# FPGA_Banks_224_225_226_227_228.net
KiCad netlist of a schematic drawn in Altium Designer
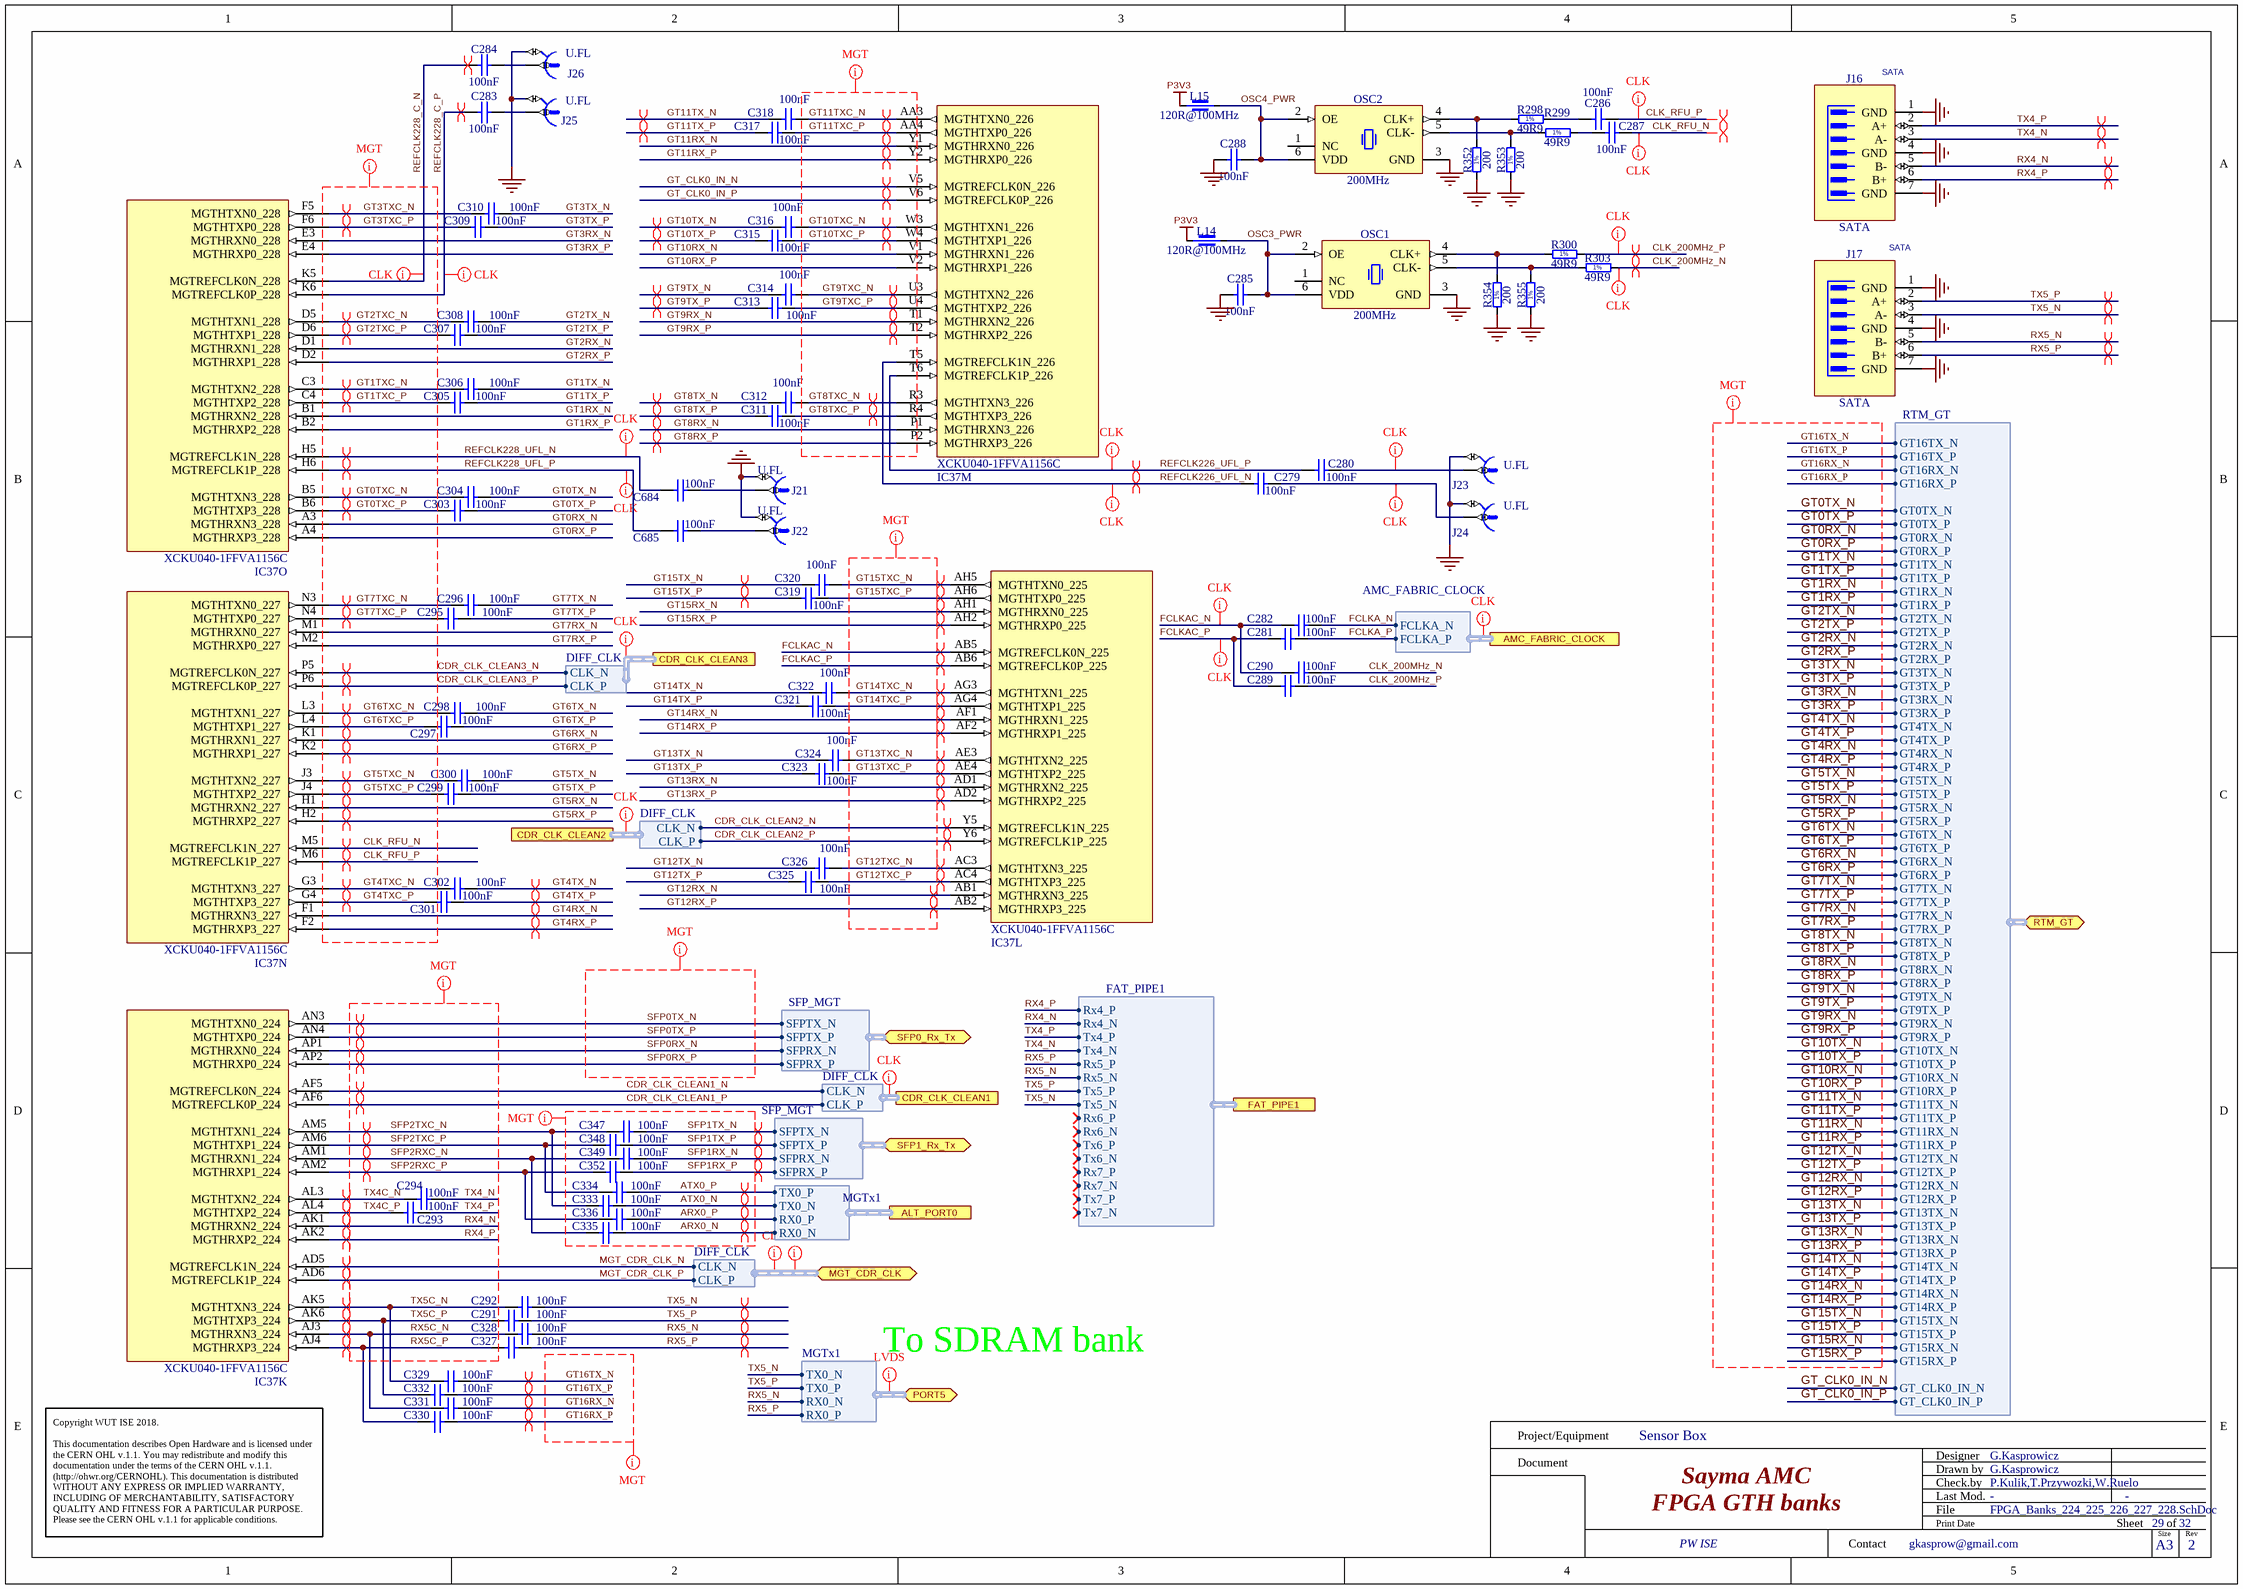
[diagram p0: FPGA_Banks_224_225_226_227_228.SchDoc]

(export (version "E")
  (design (tool "Eeschema 10.0.6"))
  (components
    (comp (ref "C279")
      (value "100nF")
      (footprint "CAPC0603X33N")
      (description "Non-polarised capacitor")
      (fields
        (field (name "MANUFACTURER PART NUMBER") "CC0201_100NF_6.3V_10%_X5R")
        (field (name "MANUFACTURER") "GENERIC")
        (field (name "AUTHOR") "CERN DEM JLC")
      )
      (libsource (lib "Capacitors") (part "Capacitor - non polarized"))
    )
    (comp (ref "C280")
      (value "100nF")
      (footprint "CAPC0603X33N")
      (description "Non-polarised capacitor")
      (fields
        (field (name "MANUFACTURER PART NUMBER") "CC0201_100NF_6.3V_10%_X5R")
        (field (name "MANUFACTURER") "GENERIC")
        (field (name "AUTHOR") "CERN DEM JLC")
      )
      (libsource (lib "Capacitors") (part "Capacitor - non polarized"))
    )
    (comp (ref "C281")
      (value "100nF")
      (footprint "CAPC0603X33N")
      (description "Non-polarised capacitor")
      (fields
        (field (name "MANUFACTURER PART NUMBER") "CC0201_100NF_6.3V_10%_X5R")
        (field (name "MANUFACTURER") "GENERIC")
        (field (name "AUTHOR") "CERN DEM JLC")
      )
      (libsource (lib "Capacitors") (part "Capacitor - non polarized"))
    )
    (comp (ref "C282")
      (value "100nF")
      (footprint "CAPC0603X33N")
      (description "Non-polarised capacitor")
      (fields
        (field (name "MANUFACTURER PART NUMBER") "CC0201_100NF_6.3V_10%_X5R")
        (field (name "MANUFACTURER") "GENERIC")
        (field (name "AUTHOR") "CERN DEM JLC")
      )
      (libsource (lib "Capacitors") (part "Capacitor - non polarized"))
    )
    (comp (ref "C283")
      (value "100nF")
      (footprint "CAPC0603X33N")
      (description "Non-polarised capacitor")
      (fields
        (field (name "MANUFACTURER PART NUMBER") "CC0201_100NF_6.3V_10%_X5R")
        (field (name "MANUFACTURER") "GENERIC")
        (field (name "AUTHOR") "CERN DEM JLC")
      )
      (libsource (lib "Capacitors") (part "Capacitor - non polarized"))
    )
    (comp (ref "C284")
      (value "100nF")
      (footprint "CAPC0603X33N")
      (description "Non-polarised capacitor")
      (fields
        (field (name "MANUFACTURER PART NUMBER") "CC0201_100NF_6.3V_10%_X5R")
        (field (name "MANUFACTURER") "GENERIC")
        (field (name "AUTHOR") "CERN DEM JLC")
      )
      (libsource (lib "Capacitors") (part "Capacitor - non polarized"))
    )
    (comp (ref "C285")
      (value "100nF")
      (footprint "CAPC0603X33N")
      (description "Non-polarised capacitor")
      (fields
        (field (name "MANUFACTURER PART NUMBER") "CC0201_100NF_6.3V_10%_X5R")
        (field (name "MANUFACTURER") "GENERIC")
        (field (name "AUTHOR") "CERN DEM JLC")
      )
      (libsource (lib "Capacitors") (part "Capacitor - non polarized"))
    )
    (comp (ref "C286")
      (value "100nF")
      (footprint "CAPC0603X33N")
      (description "Non-polarised capacitor")
      (fields
        (field (name "MANUFACTURER PART NUMBER") "CC0201_100NF_6.3V_10%_X5R")
        (field (name "MANUFACTURER") "GENERIC")
        (field (name "AUTHOR") "CERN DEM JLC")
      )
      (libsource (lib "Capacitors") (part "Capacitor - non polarized"))
    )
    (comp (ref "C287")
      (value "100nF")
      (footprint "CAPC0603X33N")
      (description "Non-polarised capacitor")
      (fields
        (field (name "MANUFACTURER PART NUMBER") "CC0201_100NF_6.3V_10%_X5R")
        (field (name "MANUFACTURER") "GENERIC")
        (field (name "AUTHOR") "CERN DEM JLC")
      )
      (libsource (lib "Capacitors") (part "Capacitor - non polarized"))
    )
    (comp (ref "C288")
      (value "100nF")
      (footprint "CAPC0603X33N")
      (description "Non-polarised capacitor")
      (fields
        (field (name "MANUFACTURER PART NUMBER") "CC0201_100NF_6.3V_10%_X5R")
        (field (name "MANUFACTURER") "GENERIC")
        (field (name "AUTHOR") "CERN DEM JLC")
      )
      (libsource (lib "Capacitors") (part "Capacitor - non polarized"))
    )
    (comp (ref "C289")
      (value "100nF")
      (footprint "CAPC0603X33N")
      (description "Non-polarised capacitor")
      (fields
        (field (name "MANUFACTURER PART NUMBER") "CC0201_100NF_6.3V_10%_X5R")
        (field (name "MANUFACTURER") "GENERIC")
        (field (name "AUTHOR") "CERN DEM JLC")
      )
      (libsource (lib "Capacitors") (part "Capacitor - non polarized"))
    )
    (comp (ref "C290")
      (value "100nF")
      (footprint "CAPC0603X33N")
      (description "Non-polarised capacitor")
      (fields
        (field (name "MANUFACTURER PART NUMBER") "CC0201_100NF_6.3V_10%_X5R")
        (field (name "MANUFACTURER") "GENERIC")
        (field (name "AUTHOR") "CERN DEM JLC")
      )
      (libsource (lib "Capacitors") (part "Capacitor - non polarized"))
    )
    (comp (ref "C291")
      (value "100nF")
      (footprint "CAPC0603X33N")
      (description "Non-polarised capacitor")
      (fields
        (field (name "MANUFACTURER PART NUMBER") "CC0201_100NF_6.3V_10%_X5R")
        (field (name "MANUFACTURER") "GENERIC")
        (field (name "AUTHOR") "CERN DEM JLC")
      )
      (libsource (lib "Capacitors") (part "Capacitor - non polarized"))
    )
    (comp (ref "C292")
      (value "100nF")
      (footprint "CAPC0603X33N")
      (description "Non-polarised capacitor")
      (fields
        (field (name "MANUFACTURER PART NUMBER") "CC0201_100NF_6.3V_10%_X5R")
        (field (name "MANUFACTURER") "GENERIC")
        (field (name "AUTHOR") "CERN DEM JLC")
      )
      (libsource (lib "Capacitors") (part "Capacitor - non polarized"))
    )
    (comp (ref "C293")
      (value "100nF")
      (footprint "CAPC0603X33N")
      (description "Non-polarised capacitor")
      (fields
        (field (name "MANUFACTURER PART NUMBER") "CC0201_100NF_6.3V_10%_X5R")
        (field (name "MANUFACTURER") "GENERIC")
        (field (name "AUTHOR") "CERN DEM JLC")
      )
      (libsource (lib "Capacitors") (part "Capacitor - non polarized"))
    )
    (comp (ref "C294")
      (value "100nF")
      (footprint "CAPC0603X33N")
      (description "Non-polarised capacitor")
      (fields
        (field (name "MANUFACTURER PART NUMBER") "CC0201_100NF_6.3V_10%_X5R")
        (field (name "MANUFACTURER") "GENERIC")
        (field (name "AUTHOR") "CERN DEM JLC")
      )
      (libsource (lib "Capacitors") (part "Capacitor - non polarized"))
    )
    (comp (ref "C295")
      (value "100nF")
      (footprint "CAPC0603X33N")
      (description "Non-polarised capacitor")
      (fields
        (field (name "MANUFACTURER PART NUMBER") "CC0201_100NF_6.3V_10%_X5R")
        (field (name "MANUFACTURER") "GENERIC")
        (field (name "AUTHOR") "CERN DEM JLC")
      )
      (libsource (lib "Capacitors") (part "Capacitor - non polarized"))
    )
    (comp (ref "C296")
      (value "100nF")
      (footprint "CAPC0603X33N")
      (description "Non-polarised capacitor")
      (fields
        (field (name "MANUFACTURER PART NUMBER") "CC0201_100NF_6.3V_10%_X5R")
        (field (name "MANUFACTURER") "GENERIC")
        (field (name "AUTHOR") "CERN DEM JLC")
      )
      (libsource (lib "Capacitors") (part "Capacitor - non polarized"))
    )
    (comp (ref "C297")
      (value "100nF")
      (footprint "CAPC0603X33N")
      (description "Non-polarised capacitor")
      (fields
        (field (name "MANUFACTURER PART NUMBER") "CC0201_100NF_6.3V_10%_X5R")
        (field (name "MANUFACTURER") "GENERIC")
        (field (name "AUTHOR") "CERN DEM JLC")
      )
      (libsource (lib "Capacitors") (part "Capacitor - non polarized"))
    )
    (comp (ref "C298")
      (value "100nF")
      (footprint "CAPC0603X33N")
      (description "Non-polarised capacitor")
      (fields
        (field (name "MANUFACTURER PART NUMBER") "CC0201_100NF_6.3V_10%_X5R")
        (field (name "MANUFACTURER") "GENERIC")
        (field (name "AUTHOR") "CERN DEM JLC")
      )
      (libsource (lib "Capacitors") (part "Capacitor - non polarized"))
    )
    (comp (ref "C299")
      (value "100nF")
      (footprint "CAPC0603X33N")
      (description "Non-polarised capacitor")
      (fields
        (field (name "MANUFACTURER PART NUMBER") "CC0201_100NF_6.3V_10%_X5R")
        (field (name "MANUFACTURER") "GENERIC")
        (field (name "AUTHOR") "CERN DEM JLC")
      )
      (libsource (lib "Capacitors") (part "Capacitor - non polarized"))
    )
    (comp (ref "C300")
      (value "100nF")
      (footprint "CAPC0603X33N")
      (description "Non-polarised capacitor")
      (fields
        (field (name "MANUFACTURER PART NUMBER") "CC0201_100NF_6.3V_10%_X5R")
        (field (name "MANUFACTURER") "GENERIC")
        (field (name "AUTHOR") "CERN DEM JLC")
      )
      (libsource (lib "Capacitors") (part "Capacitor - non polarized"))
    )
    (comp (ref "C301")
      (value "100nF")
      (footprint "CAPC0603X33N")
      (description "Non-polarised capacitor")
      (fields
        (field (name "MANUFACTURER PART NUMBER") "CC0201_100NF_6.3V_10%_X5R")
        (field (name "MANUFACTURER") "GENERIC")
        (field (name "AUTHOR") "CERN DEM JLC")
      )
      (libsource (lib "Capacitors") (part "Capacitor - non polarized"))
    )
    (comp (ref "C302")
      (value "100nF")
      (footprint "CAPC0603X33N")
      (description "Non-polarised capacitor")
      (fields
        (field (name "MANUFACTURER PART NUMBER") "CC0201_100NF_6.3V_10%_X5R")
        (field (name "MANUFACTURER") "GENERIC")
        (field (name "AUTHOR") "CERN DEM JLC")
      )
      (libsource (lib "Capacitors") (part "Capacitor - non polarized"))
    )
    (comp (ref "C303")
      (value "100nF")
      (footprint "CAPC0603X33N")
      (description "Non-polarised capacitor")
      (fields
        (field (name "MANUFACTURER PART NUMBER") "CC0201_100NF_6.3V_10%_X5R")
        (field (name "MANUFACTURER") "GENERIC")
        (field (name "AUTHOR") "CERN DEM JLC")
      )
      (libsource (lib "Capacitors") (part "Capacitor - non polarized"))
    )
    (comp (ref "C304")
      (value "100nF")
      (footprint "CAPC0603X33N")
      (description "Non-polarised capacitor")
      (fields
        (field (name "MANUFACTURER PART NUMBER") "CC0201_100NF_6.3V_10%_X5R")
        (field (name "MANUFACTURER") "GENERIC")
        (field (name "AUTHOR") "CERN DEM JLC")
      )
      (libsource (lib "Capacitors") (part "Capacitor - non polarized"))
    )
    (comp (ref "C305")
      (value "100nF")
      (footprint "CAPC0603X33N")
      (description "Non-polarised capacitor")
      (fields
        (field (name "MANUFACTURER PART NUMBER") "CC0201_100NF_6.3V_10%_X5R")
        (field (name "MANUFACTURER") "GENERIC")
        (field (name "AUTHOR") "CERN DEM JLC")
      )
      (libsource (lib "Capacitors") (part "Capacitor - non polarized"))
    )
    (comp (ref "C306")
      (value "100nF")
      (footprint "CAPC0603X33N")
      (description "Non-polarised capacitor")
      (fields
        (field (name "MANUFACTURER PART NUMBER") "CC0201_100NF_6.3V_10%_X5R")
        (field (name "MANUFACTURER") "GENERIC")
        (field (name "AUTHOR") "CERN DEM JLC")
      )
      (libsource (lib "Capacitors") (part "Capacitor - non polarized"))
    )
    (comp (ref "C307")
      (value "100nF")
      (footprint "CAPC0603X33N")
      (description "Non-polarised capacitor")
      (fields
        (field (name "MANUFACTURER PART NUMBER") "CC0201_100NF_6.3V_10%_X5R")
        (field (name "MANUFACTURER") "GENERIC")
        (field (name "AUTHOR") "CERN DEM JLC")
      )
      (libsource (lib "Capacitors") (part "Capacitor - non polarized"))
    )
    (comp (ref "C308")
      (value "100nF")
      (footprint "CAPC0603X33N")
      (description "Non-polarised capacitor")
      (fields
        (field (name "MANUFACTURER PART NUMBER") "CC0201_100NF_6.3V_10%_X5R")
        (field (name "MANUFACTURER") "GENERIC")
        (field (name "AUTHOR") "CERN DEM JLC")
      )
      (libsource (lib "Capacitors") (part "Capacitor - non polarized"))
    )
    (comp (ref "C309")
      (value "100nF")
      (footprint "CAPC0603X33N")
      (description "Non-polarised capacitor")
      (fields
        (field (name "MANUFACTURER PART NUMBER") "CC0201_100NF_6.3V_10%_X5R")
        (field (name "MANUFACTURER") "GENERIC")
        (field (name "AUTHOR") "CERN DEM JLC")
      )
      (libsource (lib "Capacitors") (part "Capacitor - non polarized"))
    )
    (comp (ref "C310")
      (value "100nF")
      (footprint "CAPC0603X33N")
      (description "Non-polarised capacitor")
      (fields
        (field (name "MANUFACTURER PART NUMBER") "CC0201_100NF_6.3V_10%_X5R")
        (field (name "MANUFACTURER") "GENERIC")
        (field (name "AUTHOR") "CERN DEM JLC")
      )
      (libsource (lib "Capacitors") (part "Capacitor - non polarized"))
    )
    (comp (ref "C311")
      (value "100nF")
      (footprint "CAPC0603X33N")
      (description "Non-polarised capacitor")
      (fields
        (field (name "MANUFACTURER PART NUMBER") "CC0201_100NF_6.3V_10%_X5R")
        (field (name "MANUFACTURER") "GENERIC")
        (field (name "AUTHOR") "CERN DEM JLC")
      )
      (libsource (lib "Capacitors") (part "Capacitor - non polarized"))
    )
    (comp (ref "C312")
      (value "100nF")
      (footprint "CAPC0603X33N")
      (description "Non-polarised capacitor")
      (fields
        (field (name "MANUFACTURER PART NUMBER") "CC0201_100NF_6.3V_10%_X5R")
        (field (name "MANUFACTURER") "GENERIC")
        (field (name "AUTHOR") "CERN DEM JLC")
      )
      (libsource (lib "Capacitors") (part "Capacitor - non polarized"))
    )
    (comp (ref "C313")
      (value "100nF")
      (footprint "CAPC0603X33N")
      (description "Non-polarised capacitor")
      (fields
        (field (name "MANUFACTURER PART NUMBER") "CC0201_100NF_6.3V_10%_X5R")
        (field (name "MANUFACTURER") "GENERIC")
        (field (name "AUTHOR") "CERN DEM JLC")
      )
      (libsource (lib "Capacitors") (part "Capacitor - non polarized"))
    )
    (comp (ref "C314")
      (value "100nF")
      (footprint "CAPC0603X33N")
      (description "Non-polarised capacitor")
      (fields
        (field (name "MANUFACTURER PART NUMBER") "CC0201_100NF_6.3V_10%_X5R")
        (field (name "MANUFACTURER") "GENERIC")
        (field (name "AUTHOR") "CERN DEM JLC")
      )
      (libsource (lib "Capacitors") (part "Capacitor - non polarized"))
    )
    (comp (ref "C315")
      (value "100nF")
      (footprint "CAPC0603X33N")
      (description "Non-polarised capacitor")
      (fields
        (field (name "MANUFACTURER PART NUMBER") "CC0201_100NF_6.3V_10%_X5R")
        (field (name "MANUFACTURER") "GENERIC")
        (field (name "AUTHOR") "CERN DEM JLC")
      )
      (libsource (lib "Capacitors") (part "Capacitor - non polarized"))
    )
    (comp (ref "C316")
      (value "100nF")
      (footprint "CAPC0603X33N")
      (description "Non-polarised capacitor")
      (fields
        (field (name "MANUFACTURER PART NUMBER") "CC0201_100NF_6.3V_10%_X5R")
        (field (name "MANUFACTURER") "GENERIC")
        (field (name "AUTHOR") "CERN DEM JLC")
      )
      (libsource (lib "Capacitors") (part "Capacitor - non polarized"))
    )
    (comp (ref "C317")
      (value "100nF")
      (footprint "CAPC0603X33N")
      (description "Non-polarised capacitor")
      (fields
        (field (name "MANUFACTURER PART NUMBER") "CC0201_100NF_6.3V_10%_X5R")
        (field (name "MANUFACTURER") "GENERIC")
        (field (name "AUTHOR") "CERN DEM JLC")
      )
      (libsource (lib "Capacitors") (part "Capacitor - non polarized"))
    )
    (comp (ref "C318")
      (value "100nF")
      (footprint "CAPC0603X33N")
      (description "Non-polarised capacitor")
      (fields
        (field (name "MANUFACTURER PART NUMBER") "CC0201_100NF_6.3V_10%_X5R")
        (field (name "MANUFACTURER") "GENERIC")
        (field (name "AUTHOR") "CERN DEM JLC")
      )
      (libsource (lib "Capacitors") (part "Capacitor - non polarized"))
    )
    (comp (ref "C319")
      (value "100nF")
      (footprint "CAPC0603X33N")
      (description "Non-polarised capacitor")
      (fields
        (field (name "MANUFACTURER PART NUMBER") "CC0201_100NF_6.3V_10%_X5R")
        (field (name "MANUFACTURER") "GENERIC")
        (field (name "AUTHOR") "CERN DEM JLC")
      )
      (libsource (lib "Capacitors") (part "Capacitor - non polarized"))
    )
    (comp (ref "C320")
      (value "100nF")
      (footprint "CAPC0603X33N")
      (description "Non-polarised capacitor")
      (fields
        (field (name "MANUFACTURER PART NUMBER") "CC0201_100NF_6.3V_10%_X5R")
        (field (name "MANUFACTURER") "GENERIC")
        (field (name "AUTHOR") "CERN DEM JLC")
      )
      (libsource (lib "Capacitors") (part "Capacitor - non polarized"))
    )
    (comp (ref "C321")
      (value "100nF")
      (footprint "CAPC0603X33N")
      (description "Non-polarised capacitor")
      (fields
        (field (name "MANUFACTURER PART NUMBER") "CC0201_100NF_6.3V_10%_X5R")
        (field (name "MANUFACTURER") "GENERIC")
        (field (name "AUTHOR") "CERN DEM JLC")
      )
      (libsource (lib "Capacitors") (part "Capacitor - non polarized"))
    )
    (comp (ref "C322")
      (value "100nF")
      (footprint "CAPC0603X33N")
      (description "Non-polarised capacitor")
      (fields
        (field (name "MANUFACTURER PART NUMBER") "CC0201_100NF_6.3V_10%_X5R")
        (field (name "MANUFACTURER") "GENERIC")
        (field (name "AUTHOR") "CERN DEM JLC")
      )
      (libsource (lib "Capacitors") (part "Capacitor - non polarized"))
    )
    (comp (ref "C323")
      (value "100nF")
      (footprint "CAPC0603X33N")
      (description "Non-polarised capacitor")
      (fields
        (field (name "MANUFACTURER PART NUMBER") "CC0201_100NF_6.3V_10%_X5R")
        (field (name "MANUFACTURER") "GENERIC")
        (field (name "AUTHOR") "CERN DEM JLC")
      )
      (libsource (lib "Capacitors") (part "Capacitor - non polarized"))
    )
    (comp (ref "C324")
      (value "100nF")
      (footprint "CAPC0603X33N")
      (description "Non-polarised capacitor")
      (fields
        (field (name "MANUFACTURER PART NUMBER") "CC0201_100NF_6.3V_10%_X5R")
        (field (name "MANUFACTURER") "GENERIC")
        (field (name "AUTHOR") "CERN DEM JLC")
      )
      (libsource (lib "Capacitors") (part "Capacitor - non polarized"))
    )
    (comp (ref "C325")
      (value "100nF")
      (footprint "CAPC0603X33N")
      (description "Non-polarised capacitor")
      (fields
        (field (name "MANUFACTURER PART NUMBER") "CC0201_100NF_6.3V_10%_X5R")
        (field (name "MANUFACTURER") "GENERIC")
        (field (name "AUTHOR") "CERN DEM JLC")
      )
      (libsource (lib "Capacitors") (part "Capacitor - non polarized"))
    )
    (comp (ref "C326")
      (value "100nF")
      (footprint "CAPC0603X33N")
      (description "Non-polarised capacitor")
      (fields
        (field (name "MANUFACTURER PART NUMBER") "CC0201_100NF_6.3V_10%_X5R")
        (field (name "MANUFACTURER") "GENERIC")
        (field (name "AUTHOR") "CERN DEM JLC")
      )
      (libsource (lib "Capacitors") (part "Capacitor - non polarized"))
    )
    (comp (ref "C327")
      (value "100nF")
      (footprint "CAPC0603X33N")
      (description "Non-polarised capacitor")
      (fields
        (field (name "MANUFACTURER PART NUMBER") "CC0201_100NF_6.3V_10%_X5R")
        (field (name "MANUFACTURER") "GENERIC")
        (field (name "AUTHOR") "CERN DEM JLC")
      )
      (libsource (lib "Capacitors") (part "Capacitor - non polarized"))
    )
    (comp (ref "C328")
      (value "100nF")
      (footprint "CAPC0603X33N")
      (description "Non-polarised capacitor")
      (fields
        (field (name "MANUFACTURER PART NUMBER") "CC0201_100NF_6.3V_10%_X5R")
        (field (name "MANUFACTURER") "GENERIC")
        (field (name "AUTHOR") "CERN DEM JLC")
      )
      (libsource (lib "Capacitors") (part "Capacitor - non polarized"))
    )
    (comp (ref "C329")
      (value "100nF")
      (footprint "CAPC0603X33N")
      (description "Non-polarised capacitor")
      (fields
        (field (name "MANUFACTURER PART NUMBER") "CC0201_100NF_6.3V_10%_X5R")
        (field (name "MANUFACTURER") "GENERIC")
        (field (name "AUTHOR") "CERN DEM JLC")
      )
      (libsource (lib "Capacitors") (part "Capacitor - non polarized"))
    )
    (comp (ref "C330")
      (value "100nF")
      (footprint "CAPC0603X33N")
      (description "Non-polarised capacitor")
      (fields
        (field (name "MANUFACTURER PART NUMBER") "CC0201_100NF_6.3V_10%_X5R")
        (field (name "MANUFACTURER") "GENERIC")
        (field (name "AUTHOR") "CERN DEM JLC")
      )
      (libsource (lib "Capacitors") (part "Capacitor - non polarized"))
    )
    (comp (ref "C331")
      (value "100nF")
      (footprint "CAPC0603X33N")
      (description "Non-polarised capacitor")
      (fields
        (field (name "MANUFACTURER PART NUMBER") "CC0201_100NF_6.3V_10%_X5R")
        (field (name "MANUFACTURER") "GENERIC")
        (field (name "AUTHOR") "CERN DEM JLC")
      )
      (libsource (lib "Capacitors") (part "Capacitor - non polarized"))
    )
    (comp (ref "C332")
      (value "100nF")
      (footprint "CAPC0603X33N")
      (description "Non-polarised capacitor")
      (fields
        (field (name "MANUFACTURER PART NUMBER") "CC0201_100NF_6.3V_10%_X5R")
        (field (name "MANUFACTURER") "GENERIC")
        (field (name "AUTHOR") "CERN DEM JLC")
      )
      (libsource (lib "Capacitors") (part "Capacitor - non polarized"))
    )
    (comp (ref "C333")
      (value "100nF")
      (footprint "CAPC0603X33N")
      (description "Non-polarised capacitor")
      (fields
        (field (name "MANUFACTURER PART NUMBER") "CC0201_100NF_6.3V_10%_X5R")
        (field (name "MANUFACTURER") "GENERIC")
        (field (name "AUTHOR") "CERN DEM JLC")
      )
      (libsource (lib "Capacitors") (part "Capacitor - non polarized"))
    )
    (comp (ref "C334")
      (value "100nF")
      (footprint "CAPC0603X33N")
      (description "Non-polarised capacitor")
      (fields
        (field (name "MANUFACTURER PART NUMBER") "CC0201_100NF_6.3V_10%_X5R")
        (field (name "MANUFACTURER") "GENERIC")
        (field (name "AUTHOR") "CERN DEM JLC")
      )
      (libsource (lib "Capacitors") (part "Capacitor - non polarized"))
    )
    (comp (ref "C335")
      (value "100nF")
      (footprint "CAPC0603X33N")
      (description "Non-polarised capacitor")
      (fields
        (field (name "MANUFACTURER PART NUMBER") "CC0201_100NF_6.3V_10%_X5R")
        (field (name "MANUFACTURER") "GENERIC")
        (field (name "AUTHOR") "CERN DEM JLC")
      )
      (libsource (lib "Capacitors") (part "Capacitor - non polarized"))
    )
    (comp (ref "C336")
      (value "100nF")
      (footprint "CAPC0603X33N")
      (description "Non-polarised capacitor")
      (fields
        (field (name "MANUFACTURER PART NUMBER") "CC0201_100NF_6.3V_10%_X5R")
        (field (name "MANUFACTURER") "GENERIC")
        (field (name "AUTHOR") "CERN DEM JLC")
      )
      (libsource (lib "Capacitors") (part "Capacitor - non polarized"))
    )
    (comp (ref "C347")
      (value "100nF")
      (footprint "CAPC0603X33N")
      (description "Non-polarised capacitor")
      (fields
        (field (name "MANUFACTURER PART NUMBER") "CC0201_100NF_6.3V_10%_X5R")
        (field (name "MANUFACTURER") "GENERIC")
        (field (name "AUTHOR") "CERN DEM JLC")
      )
      (libsource (lib "Capacitors") (part "Capacitor - non polarized"))
    )
    (comp (ref "C348")
      (value "100nF")
      (footprint "CAPC0603X33N")
      (description "Non-polarised capacitor")
      (fields
        (field (name "MANUFACTURER PART NUMBER") "CC0201_100NF_6.3V_10%_X5R")
        (field (name "MANUFACTURER") "GENERIC")
        (field (name "AUTHOR") "CERN DEM JLC")
      )
      (libsource (lib "Capacitors") (part "Capacitor - non polarized"))
    )
    (comp (ref "C349")
      (value "100nF")
      (footprint "CAPC0603X33N")
      (description "Non-polarised capacitor")
      (fields
        (field (name "MANUFACTURER PART NUMBER") "CC0201_100NF_6.3V_10%_X5R")
        (field (name "MANUFACTURER") "GENERIC")
        (field (name "AUTHOR") "CERN DEM JLC")
      )
      (libsource (lib "Capacitors") (part "Capacitor - non polarized"))
    )
    (comp (ref "C352")
      (value "100nF")
      (footprint "CAPC0603X33N")
      (description "Non-polarised capacitor")
      (fields
        (field (name "MANUFACTURER PART NUMBER") "CC0201_100NF_6.3V_10%_X5R")
        (field (name "MANUFACTURER") "GENERIC")
        (field (name "AUTHOR") "CERN DEM JLC")
      )
      (libsource (lib "Capacitors") (part "Capacitor - non polarized"))
    )
    (comp (ref "C684")
      (value "100nF")
      (footprint "CAPC1005X55N")
      (description "Non-polarised capacitor")
      (fields
        (field (name "MANUFACTURER PART NUMBER") "CC0402_100NF_16V_10%_X5R")
        (field (name "MANUFACTURER") "GENERIC")
        (field (name "AUTHOR") "CERN DEM JLC")
      )
      (libsource (lib "Capacitors") (part "Capacitor - non polarized"))
    )
    (comp (ref "C685")
      (value "100nF")
      (footprint "CAPC1005X55N")
      (description "Non-polarised capacitor")
      (fields
        (field (name "MANUFACTURER PART NUMBER") "CC0402_100NF_16V_10%_X5R")
        (field (name "MANUFACTURER") "GENERIC")
        (field (name "AUTHOR") "CERN DEM JLC")
      )
      (libsource (lib "Capacitors") (part "Capacitor - non polarized"))
    )
    (comp (ref "IC37")
      (value "XCKU040-1FFVA1156C")
      (footprint "BGA1156C100P34X34_3500X3500X350")
      (description "Kintex UltraScale FPGA, 520 I/O, 530K Cells, 1156-Ball BGA, Speed Grade 1, Commercial Grade")
      (fields (field (name "MANUFACTURER") "XILINX") (field (name "AUTHOR") "CERN DEM CA"))
      (libsource (lib "") (part "XCKU040-1FFVA1156C_1"))
    )
    (comp (ref "J16")
      (value "SATA")
      (footprint "MOLEX_67800-5005")
      (description "7 Pin SATA Receptacle")
      (fields
        (field (name "MANUFACTURER PART NUMBER") "67800-5005")
        (field (name "MANUFACTURER") "MOLEX")
        (field (name "AUTHOR") "CERN DEM MR")
      )
      (libsource (lib "Connectors") (part "Connector SATA 7 Male"))
    )
    (comp (ref "J17")
      (value "SATA")
      (footprint "MOLEX_67800-5005")
      (description "7 Pin SATA Receptacle")
      (fields
        (field (name "MANUFACTURER PART NUMBER") "67800-5005")
        (field (name "MANUFACTURER") "MOLEX")
        (field (name "AUTHOR") "CERN DEM MR")
      )
      (libsource (lib "Connectors") (part "Connector SATA 7 Male"))
    )
    (comp (ref "J21")
      (value "U.FL")
      (footprint "HIROSE_U.FL-R-SMT-1(10)")
      (fields
        (field (name "PART NUMBER") "HIROSE_U.FL-R-SMT-1(10)")
        (field (name "MANUFACTURER") "HIROSE (HRS)")
        (field (name "MANUFACTURER PART NUMBER") "U.FL-R-SMT-1(10)")
        (field (name "AUTHOR") "CERN DEM JLC")
      )
      (libsource (lib "Connectors") (part "Coax_1Male_1Shield"))
    )
    (comp (ref "J22")
      (value "U.FL")
      (footprint "HIROSE_U.FL-R-SMT-1(10)")
      (fields
        (field (name "PART NUMBER") "HIROSE_U.FL-R-SMT-1(10)")
        (field (name "MANUFACTURER") "HIROSE (HRS)")
        (field (name "MANUFACTURER PART NUMBER") "U.FL-R-SMT-1(10)")
        (field (name "AUTHOR") "CERN DEM JLC")
      )
      (libsource (lib "Connectors") (part "Coax_1Male_1Shield"))
    )
    (comp (ref "J23")
      (value "U.FL")
      (footprint "HIROSE_U.FL-R-SMT-1(10)")
      (fields
        (field (name "MANUFACTURER PART NUMBER") "U.FL-R-SMT-1(10)")
        (field (name "MANUFACTURER") "HIROSE (HRS)")
        (field (name "PART NUMBER") "HIROSE_U.FL-R-SMT-1(10)")
        (field (name "AUTHOR") "CERN DEM JLC")
      )
      (libsource (lib "Connectors") (part "Coax_1Male_1Shield"))
    )
    (comp (ref "J24")
      (value "U.FL")
      (footprint "HIROSE_U.FL-R-SMT-1(10)")
      (fields
        (field (name "MANUFACTURER PART NUMBER") "U.FL-R-SMT-1(10)")
        (field (name "MANUFACTURER") "HIROSE (HRS)")
        (field (name "PART NUMBER") "HIROSE_U.FL-R-SMT-1(10)")
        (field (name "AUTHOR") "CERN DEM JLC")
      )
      (libsource (lib "Connectors") (part "Coax_1Male_1Shield"))
    )
    (comp (ref "J25")
      (value "U.FL")
      (footprint "HIROSE_U.FL-R-SMT-1(10)")
      (fields
        (field (name "MANUFACTURER PART NUMBER") "U.FL-R-SMT-1(10)")
        (field (name "MANUFACTURER") "HIROSE (HRS)")
        (field (name "PART NUMBER") "HIROSE_U.FL-R-SMT-1(10)")
        (field (name "AUTHOR") "CERN DEM JLC")
      )
      (libsource (lib "Connectors") (part "Coax_1Male_1Shield"))
    )
    (comp (ref "J26")
      (value "U.FL")
      (footprint "HIROSE_U.FL-R-SMT-1(10)")
      (fields
        (field (name "MANUFACTURER PART NUMBER") "U.FL-R-SMT-1(10)")
        (field (name "MANUFACTURER") "HIROSE (HRS)")
        (field (name "PART NUMBER") "HIROSE_U.FL-R-SMT-1(10)")
        (field (name "AUTHOR") "CERN DEM JLC")
      )
      (libsource (lib "Connectors") (part "Coax_1Male_1Shield"))
    )
    (comp (ref "L14")
      (value "120R@100MHz")
      (footprint "INDC1005X55N")
      (fields
        (field (name "MANUFACTURER PART NUMBER") "BLM15PX121SN1D")
        (field (name "MANUFACTURER") "MURATA")
        (field (name "PART NUMBER") "IND0402_MURATA_BLM15PX121SN1D")
        (field (name "AUTHOR") "CERN DEM JMW")
      )
      (libsource (lib "Inductors & Transformers") (part "Ferrite Bead"))
    )
    (comp (ref "L15")
      (value "120R@100MHz")
      (footprint "INDC1005X55N")
      (fields
        (field (name "MANUFACTURER PART NUMBER") "BLM15PX121SN1D")
        (field (name "MANUFACTURER") "MURATA")
        (field (name "PART NUMBER") "IND0402_MURATA_BLM15PX121SN1D")
        (field (name "AUTHOR") "CERN DEM JMW")
      )
      (libsource (lib "Inductors & Transformers") (part "Ferrite Bead"))
    )
    (comp (ref "OSC1")
      (value "200MHz")
      (footprint "OSC_SILICON-LAB_SI510-6N(5X7)")
      (description "Crystal Oscillator 6 pins, Si510 (LVDS/LVPECL/HCSL/Dual CMOS)")
      (fields
        (field (name "MANUFACTURER PART NUMBER") "510ABA200M000AAG")
        (field (name "MANUFACTURER") "SILICON LABS")
        (field (name "AUTHOR") "GK")
      )
      (libsource (lib "LIBRARY_SCH") (part "OSC_200MHZ_SILICON-LAB_510ABA200M000AAG"))
    )
    (comp (ref "OSC2")
      (value "200MHz")
      (footprint "OSC_SILICON-LAB_SI510-6N(5X7)")
      (description "Crystal Oscillator 6 pins, Si510 (LVDS/LVPECL/HCSL/Dual CMOS)")
      (fields
        (field (name "MANUFACTURER PART NUMBER") "510ABA200M000AAG")
        (field (name "MANUFACTURER") "SILICON LABS")
        (field (name "AUTHOR") "GK")
      )
      (libsource (lib "LIBRARY_SCH") (part "OSC_200MHZ_SILICON-LAB_510ABA200M000AAG"))
    )
    (comp (ref "R298")
      (value "49R9")
      (footprint "RESC1005X40N")
      (description "Resistor - 1%")
      (fields
        (field (name "MANUFACTURER PART NUMBER") "R0402_49R9_1%_0.0625W_100PPM")
        (field (name "MANUFACTURER") "GENERIC")
        (field (name "AUTHOR") "CERN DEM JLC")
      )
      (libsource (lib "Resistors") (part "Resistor - 1%"))
    )
    (comp (ref "R299")
      (value "49R9")
      (footprint "RESC1005X40N")
      (description "Resistor - 1%")
      (fields
        (field (name "MANUFACTURER PART NUMBER") "R0402_49R9_1%_0.0625W_100PPM")
        (field (name "MANUFACTURER") "GENERIC")
        (field (name "AUTHOR") "CERN DEM JLC")
      )
      (libsource (lib "Resistors") (part "Resistor - 1%"))
    )
    (comp (ref "R300")
      (value "49R9")
      (footprint "RESC1005X40N")
      (description "Resistor - 1%")
      (fields
        (field (name "MANUFACTURER PART NUMBER") "R0402_49R9_1%_0.0625W_100PPM")
        (field (name "MANUFACTURER") "GENERIC")
        (field (name "AUTHOR") "CERN DEM JLC")
      )
      (libsource (lib "Resistors") (part "Resistor - 1%"))
    )
    (comp (ref "R303")
      (value "49R9")
      (footprint "RESC1005X40N")
      (description "Resistor - 1%")
      (fields
        (field (name "MANUFACTURER PART NUMBER") "R0402_49R9_1%_0.0625W_100PPM")
        (field (name "MANUFACTURER") "GENERIC")
        (field (name "AUTHOR") "CERN DEM JLC")
      )
      (libsource (lib "Resistors") (part "Resistor - 1%"))
    )
    (comp (ref "R352")
      (value "200")
      (footprint "RESC1005X40N")
      (description "Resistor - 1%")
      (fields
        (field (name "MANUFACTURER PART NUMBER") "R0402_200R_1%_0.0625W_100PPM")
        (field (name "MANUFACTURER") "GENERIC")
        (field (name "AUTHOR") "CERN DEM JLC")
      )
      (libsource (lib "Resistors") (part "Resistor - 1%"))
    )
    (comp (ref "R353")
      (value "200")
      (footprint "RESC1005X40N")
      (description "Resistor - 1%")
      (fields
        (field (name "MANUFACTURER PART NUMBER") "R0402_200R_1%_0.0625W_100PPM")
        (field (name "MANUFACTURER") "GENERIC")
        (field (name "AUTHOR") "CERN DEM JLC")
      )
      (libsource (lib "Resistors") (part "Resistor - 1%"))
    )
    (comp (ref "R354")
      (value "200")
      (footprint "RESC1005X40N")
      (description "Resistor - 1%")
      (fields
        (field (name "MANUFACTURER PART NUMBER") "R0402_200R_1%_0.0625W_100PPM")
        (field (name "MANUFACTURER") "GENERIC")
        (field (name "AUTHOR") "CERN DEM JLC")
      )
      (libsource (lib "Resistors") (part "Resistor - 1%"))
    )
    (comp (ref "R355")
      (value "200")
      (footprint "RESC1005X40N")
      (description "Resistor - 1%")
      (fields
        (field (name "MANUFACTURER PART NUMBER") "R0402_200R_1%_0.0625W_100PPM")
        (field (name "MANUFACTURER") "GENERIC")
        (field (name "AUTHOR") "CERN DEM JLC")
      )
      (libsource (lib "Resistors") (part "Resistor - 1%"))
    )
  )
  (nets
    (net (code "7") (name "/ARX0_N") (class "Default")
      (node (ref "C335") (pin "2") (pinfunction "2_2") (pintype "passive"))
    )
    (net (code "8") (name "/ARX0_P") (class "Default")
      (node (ref "C336") (pin "2") (pinfunction "2_2") (pintype "passive"))
    )
    (net (code "9") (name "/ATX0_N") (class "Default")
      (node (ref "C333") (pin "2") (pinfunction "2_2") (pintype "passive"))
    )
    (net (code "10") (name "/ATX0_P") (class "Default")
      (node (ref "C334") (pin "2") (pinfunction "2_2") (pintype "passive"))
    )
    (net (code "11") (name "/CDR_CLK_CLEAN1_N") (class "Default")
      (node (ref "IC37") (pin "AF5") (pinfunction "MGTREFCLK0N_224_AF5") (pintype "input"))
    )
    (net (code "12") (name "/CDR_CLK_CLEAN1_P") (class "Default")
      (node (ref "IC37") (pin "AF6") (pinfunction "MGTREFCLK0P_224_AF6") (pintype "input"))
    )
    (net (code "13") (name "/CDR_CLK_CLEAN2_N") (class "Default")
      (node (ref "IC37") (pin "Y5") (pinfunction "MGTREFCLK1N_225_Y5") (pintype "input"))
    )
    (net (code "14") (name "/CDR_CLK_CLEAN2_P") (class "Default")
      (node (ref "IC37") (pin "Y6") (pinfunction "MGTREFCLK1P_225_Y6") (pintype "input"))
    )
    (net (code "15") (name "/CDR_CLK_CLEAN3_N") (class "Default")
      (node (ref "IC37") (pin "P5") (pinfunction "MGTREFCLK0N_227_P5") (pintype "input"))
    )
    (net (code "16") (name "/CDR_CLK_CLEAN3_P") (class "Default")
      (node (ref "IC37") (pin "P6") (pinfunction "MGTREFCLK0P_227_P6") (pintype "input"))
    )
    (net (code "17") (name "/CLK_200MHz_N") (class "Default")
      (node (ref "C290") (pin "2") (pinfunction "2_2") (pintype "passive"))
      (node (ref "R303") (pin "2") (pinfunction "2_2") (pintype "passive"))
    )
    (net (code "18") (name "/CLK_200MHz_P") (class "Default")
      (node (ref "C289") (pin "2") (pinfunction "2_2") (pintype "passive"))
      (node (ref "R300") (pin "2") (pinfunction "2_2") (pintype "passive"))
    )
    (net (code "19") (name "/CLK_RFU_N") (class "Default")
      (node (ref "C287") (pin "2") (pinfunction "2_2") (pintype "passive"))
      (node (ref "IC37") (pin "M5") (pinfunction "MGTREFCLK1N_227_M5") (pintype "input"))
    )
    (net (code "20") (name "/CLK_RFU_P") (class "Default")
      (node (ref "C286") (pin "2") (pinfunction "2_2") (pintype "passive"))
      (node (ref "IC37") (pin "M6") (pinfunction "MGTREFCLK1P_227_M6") (pintype "input"))
    )
    (net (code "21") (name "/FCLKAC_N") (class "Default")
      (node (ref "C282") (pin "1") (pinfunction "1_1") (pintype "passive"))
      (node (ref "C290") (pin "1") (pinfunction "1_1") (pintype "passive"))
      (node (ref "IC37") (pin "AB5") (pinfunction "MGTREFCLK0N_225_AB5") (pintype "input"))
    )
    (net (code "22") (name "/FCLKAC_P") (class "Default")
      (node (ref "C281") (pin "1") (pinfunction "1_1") (pintype "passive"))
      (node (ref "C289") (pin "1") (pinfunction "1_1") (pintype "passive"))
      (node (ref "IC37") (pin "AB6") (pinfunction "MGTREFCLK0P_225_AB6") (pintype "input"))
    )
    (net (code "23") (name "/FCLKA_N") (class "Default")
      (node (ref "C282") (pin "2") (pinfunction "2_2") (pintype "passive"))
    )
    (net (code "24") (name "/FCLKA_P") (class "Default")
      (node (ref "C281") (pin "2") (pinfunction "2_2") (pintype "passive"))
    )
    (net (code "25") (name "/GT0RX_N") (class "Default")
      (node (ref "IC37") (pin "A3") (pinfunction "MGTHRXN3_228_A3") (pintype "input"))
    )
    (net (code "26") (name "/GT0RX_P") (class "Default")
      (node (ref "IC37") (pin "A4") (pinfunction "MGTHRXP3_228_A4") (pintype "input"))
    )
    (net (code "27") (name "/GT0TXC_N") (class "Default")
      (node (ref "C304") (pin "1") (pinfunction "1_1") (pintype "passive"))
      (node (ref "IC37") (pin "B5") (pinfunction "MGTHTXN3_228_B5") (pintype "output"))
    )
    (net (code "28") (name "/GT0TXC_P") (class "Default")
      (node (ref "C303") (pin "1") (pinfunction "1_1") (pintype "passive"))
      (node (ref "IC37") (pin "B6") (pinfunction "MGTHTXP3_228_B6") (pintype "output"))
    )
    (net (code "29") (name "/GT0TX_N") (class "Default")
      (node (ref "C304") (pin "2") (pinfunction "2_2") (pintype "passive"))
    )
    (net (code "30") (name "/GT0TX_P") (class "Default")
      (node (ref "C303") (pin "2") (pinfunction "2_2") (pintype "passive"))
    )
    (net (code "31") (name "/GT1RX_N") (class "Default")
      (node (ref "IC37") (pin "B1") (pinfunction "MGTHRXN2_228_B1") (pintype "input"))
    )
    (net (code "32") (name "/GT1RX_P") (class "Default")
      (node (ref "IC37") (pin "B2") (pinfunction "MGTHRXP2_228_B2") (pintype "input"))
    )
    (net (code "33") (name "/GT1TXC_N") (class "Default")
      (node (ref "C306") (pin "1") (pinfunction "1_1") (pintype "passive"))
      (node (ref "IC37") (pin "C3") (pinfunction "MGTHTXN2_228_C3") (pintype "output"))
    )
    (net (code "34") (name "/GT1TXC_P") (class "Default")
      (node (ref "C305") (pin "1") (pinfunction "1_1") (pintype "passive"))
      (node (ref "IC37") (pin "C4") (pinfunction "MGTHTXP2_228_C4") (pintype "output"))
    )
    (net (code "35") (name "/GT1TX_N") (class "Default")
      (node (ref "C306") (pin "2") (pinfunction "2_2") (pintype "passive"))
    )
    (net (code "36") (name "/GT1TX_P") (class "Default")
      (node (ref "C305") (pin "2") (pinfunction "2_2") (pintype "passive"))
    )
    (net (code "37") (name "/GT2RX_N") (class "Default")
      (node (ref "IC37") (pin "D1") (pinfunction "MGTHRXN1_228_D1") (pintype "input"))
    )
    (net (code "38") (name "/GT2RX_P") (class "Default")
      (node (ref "IC37") (pin "D2") (pinfunction "MGTHRXP1_228_D2") (pintype "input"))
    )
    (net (code "39") (name "/GT2TXC_N") (class "Default")
      (node (ref "C308") (pin "1") (pinfunction "1_1") (pintype "passive"))
      (node (ref "IC37") (pin "D5") (pinfunction "MGTHTXN1_228_D5") (pintype "output"))
    )
    (net (code "40") (name "/GT2TXC_P") (class "Default")
      (node (ref "C307") (pin "1") (pinfunction "1_1") (pintype "passive"))
      (node (ref "IC37") (pin "D6") (pinfunction "MGTHTXP1_228_D6") (pintype "output"))
    )
    (net (code "41") (name "/GT2TX_N") (class "Default")
      (node (ref "C308") (pin "2") (pinfunction "2_2") (pintype "passive"))
    )
    (net (code "42") (name "/GT2TX_P") (class "Default")
      (node (ref "C307") (pin "2") (pinfunction "2_2") (pintype "passive"))
    )
    (net (code "43") (name "/GT3RX_N") (class "Default")
      (node (ref "IC37") (pin "E3") (pinfunction "MGTHRXN0_228_E3") (pintype "input"))
    )
    (net (code "44") (name "/GT3RX_P") (class "Default")
      (node (ref "IC37") (pin "E4") (pinfunction "MGTHRXP0_228_E4") (pintype "input"))
    )
    (net (code "45") (name "/GT3TXC_N") (class "Default")
      (node (ref "C310") (pin "1") (pinfunction "1_1") (pintype "passive"))
      (node (ref "IC37") (pin "F5") (pinfunction "MGTHTXN0_228_F5") (pintype "output"))
    )
    (net (code "46") (name "/GT3TXC_P") (class "Default")
      (node (ref "C309") (pin "1") (pinfunction "1_1") (pintype "passive"))
      (node (ref "IC37") (pin "F6") (pinfunction "MGTHTXP0_228_F6") (pintype "output"))
    )
    (net (code "47") (name "/GT3TX_N") (class "Default")
      (node (ref "C310") (pin "2") (pinfunction "2_2") (pintype "passive"))
    )
    (net (code "48") (name "/GT3TX_P") (class "Default")
      (node (ref "C309") (pin "2") (pinfunction "2_2") (pintype "passive"))
    )
    (net (code "49") (name "/GT4RX_N") (class "Default")
      (node (ref "IC37") (pin "F1") (pinfunction "MGTHRXN3_227_F1") (pintype "input"))
    )
    (net (code "50") (name "/GT4RX_P") (class "Default")
      (node (ref "IC37") (pin "F2") (pinfunction "MGTHRXP3_227_F2") (pintype "input"))
    )
    (net (code "51") (name "/GT4TXC_N") (class "Default")
      (node (ref "C302") (pin "1") (pinfunction "1_1") (pintype "passive"))
      (node (ref "IC37") (pin "G3") (pinfunction "MGTHTXN3_227_G3") (pintype "output"))
    )
    (net (code "52") (name "/GT4TXC_P") (class "Default")
      (node (ref "C301") (pin "1") (pinfunction "1_1") (pintype "passive"))
      (node (ref "IC37") (pin "G4") (pinfunction "MGTHTXP3_227_G4") (pintype "output"))
    )
    (net (code "53") (name "/GT4TX_N") (class "Default")
      (node (ref "C302") (pin "2") (pinfunction "2_2") (pintype "passive"))
    )
    (net (code "54") (name "/GT4TX_P") (class "Default")
      (node (ref "C301") (pin "2") (pinfunction "2_2") (pintype "passive"))
    )
    (net (code "55") (name "/GT5RX_N") (class "Default")
      (node (ref "IC37") (pin "H1") (pinfunction "MGTHRXN2_227_H1") (pintype "input"))
    )
    (net (code "56") (name "/GT5RX_P") (class "Default")
      (node (ref "IC37") (pin "H2") (pinfunction "MGTHRXP2_227_H2") (pintype "input"))
    )
    (net (code "57") (name "/GT5TXC_N") (class "Default")
      (node (ref "C300") (pin "1") (pinfunction "1_1") (pintype "passive"))
      (node (ref "IC37") (pin "J3") (pinfunction "MGTHTXN2_227_J3") (pintype "output"))
    )
    (net (code "58") (name "/GT5TXC_P") (class "Default")
      (node (ref "C299") (pin "1") (pinfunction "1_1") (pintype "passive"))
      (node (ref "IC37") (pin "J4") (pinfunction "MGTHTXP2_227_J4") (pintype "output"))
    )
    (net (code "59") (name "/GT5TX_N") (class "Default")
      (node (ref "C300") (pin "2") (pinfunction "2_2") (pintype "passive"))
    )
    (net (code "60") (name "/GT5TX_P") (class "Default")
      (node (ref "C299") (pin "2") (pinfunction "2_2") (pintype "passive"))
    )
    (net (code "61") (name "/GT6RX_N") (class "Default")
      (node (ref "IC37") (pin "K1") (pinfunction "MGTHRXN1_227_K1") (pintype "input"))
    )
    (net (code "62") (name "/GT6RX_P") (class "Default")
      (node (ref "IC37") (pin "K2") (pinfunction "MGTHRXP1_227_K2") (pintype "input"))
    )
    (net (code "63") (name "/GT6TXC_N") (class "Default")
      (node (ref "C298") (pin "1") (pinfunction "1_1") (pintype "passive"))
      (node (ref "IC37") (pin "L3") (pinfunction "MGTHTXN1_227_L3") (pintype "output"))
    )
    (net (code "64") (name "/GT6TXC_P") (class "Default")
      (node (ref "C297") (pin "1") (pinfunction "1_1") (pintype "passive"))
      (node (ref "IC37") (pin "L4") (pinfunction "MGTHTXP1_227_L4") (pintype "output"))
    )
    (net (code "65") (name "/GT6TX_N") (class "Default")
      (node (ref "C298") (pin "2") (pinfunction "2_2") (pintype "passive"))
    )
    (net (code "66") (name "/GT6TX_P") (class "Default")
      (node (ref "C297") (pin "2") (pinfunction "2_2") (pintype "passive"))
    )
    (net (code "67") (name "/GT7RX_N") (class "Default")
      (node (ref "IC37") (pin "M1") (pinfunction "MGTHRXN0_227_M1") (pintype "input"))
    )
    (net (code "68") (name "/GT7RX_P") (class "Default")
      (node (ref "IC37") (pin "M2") (pinfunction "MGTHRXP0_227_M2") (pintype "input"))
    )
    (net (code "69") (name "/GT7TXC_N") (class "Default")
      (node (ref "C296") (pin "1") (pinfunction "1_1") (pintype "passive"))
      (node (ref "IC37") (pin "N3") (pinfunction "MGTHTXN0_227_N3") (pintype "output"))
    )
    (net (code "70") (name "/GT7TXC_P") (class "Default")
      (node (ref "C295") (pin "1") (pinfunction "1_1") (pintype "passive"))
      (node (ref "IC37") (pin "N4") (pinfunction "MGTHTXP0_227_N4") (pintype "output"))
    )
    (net (code "71") (name "/GT7TX_N") (class "Default")
      (node (ref "C296") (pin "2") (pinfunction "2_2") (pintype "passive"))
    )
    (net (code "72") (name "/GT7TX_P") (class "Default")
      (node (ref "C295") (pin "2") (pinfunction "2_2") (pintype "passive"))
    )
    (net (code "73") (name "/GT8RX_N") (class "Default")
      (node (ref "IC37") (pin "P1") (pinfunction "MGTHRXN3_226_P1") (pintype "input"))
    )
    (net (code "74") (name "/GT8RX_P") (class "Default")
      (node (ref "IC37") (pin "P2") (pinfunction "MGTHRXP3_226_P2") (pintype "input"))
    )
    (net (code "75") (name "/GT8TXC_N") (class "Default")
      (node (ref "C312") (pin "2") (pinfunction "2_2") (pintype "passive"))
      (node (ref "IC37") (pin "R3") (pinfunction "MGTHTXN3_226_R3") (pintype "output"))
    )
    (net (code "76") (name "/GT8TXC_P") (class "Default")
      (node (ref "C311") (pin "2") (pinfunction "2_2") (pintype "passive"))
      (node (ref "IC37") (pin "R4") (pinfunction "MGTHTXP3_226_R4") (pintype "output"))
    )
    (net (code "77") (name "/GT8TX_N") (class "Default")
      (node (ref "C312") (pin "1") (pinfunction "1_1") (pintype "passive"))
    )
    (net (code "78") (name "/GT8TX_P") (class "Default")
      (node (ref "C311") (pin "1") (pinfunction "1_1") (pintype "passive"))
    )
    (net (code "79") (name "/GT9RX_N") (class "Default")
      (node (ref "IC37") (pin "T1") (pinfunction "MGTHRXN2_226_T1") (pintype "input"))
    )
    (net (code "80") (name "/GT9RX_P") (class "Default")
      (node (ref "IC37") (pin "T2") (pinfunction "MGTHRXP2_226_T2") (pintype "input"))
    )
    (net (code "81") (name "/GT9TXC_N") (class "Default")
      (node (ref "C314") (pin "2") (pinfunction "2_2") (pintype "passive"))
      (node (ref "IC37") (pin "U3") (pinfunction "MGTHTXN2_226_U3") (pintype "output"))
    )
    (net (code "82") (name "/GT9TXC_P") (class "Default")
      (node (ref "C313") (pin "2") (pinfunction "2_2") (pintype "passive"))
      (node (ref "IC37") (pin "U4") (pinfunction "MGTHTXP2_226_U4") (pintype "output"))
    )
    (net (code "83") (name "/GT9TX_N") (class "Default")
      (node (ref "C314") (pin "1") (pinfunction "1_1") (pintype "passive"))
    )
    (net (code "84") (name "/GT9TX_P") (class "Default")
      (node (ref "C313") (pin "1") (pinfunction "1_1") (pintype "passive"))
    )
    (net (code "85") (name "/GT10RX_N") (class "Default")
      (node (ref "IC37") (pin "V1") (pinfunction "MGTHRXN1_226_V1") (pintype "input"))
    )
    (net (code "86") (name "/GT10RX_P") (class "Default")
      (node (ref "IC37") (pin "V2") (pinfunction "MGTHRXP1_226_V2") (pintype "input"))
    )
    (net (code "87") (name "/GT10TXC_N") (class "Default")
      (node (ref "C316") (pin "2") (pinfunction "2_2") (pintype "passive"))
      (node (ref "IC37") (pin "W3") (pinfunction "MGTHTXN1_226_W3") (pintype "output"))
    )
    (net (code "88") (name "/GT10TXC_P") (class "Default")
      (node (ref "C315") (pin "2") (pinfunction "2_2") (pintype "passive"))
      (node (ref "IC37") (pin "W4") (pinfunction "MGTHTXP1_226_W4") (pintype "output"))
    )
    (net (code "89") (name "/GT10TX_N") (class "Default")
      (node (ref "C316") (pin "1") (pinfunction "1_1") (pintype "passive"))
    )
    (net (code "90") (name "/GT10TX_P") (class "Default")
      (node (ref "C315") (pin "1") (pinfunction "1_1") (pintype "passive"))
    )
    (net (code "91") (name "/GT11RX_N") (class "Default")
      (node (ref "IC37") (pin "Y1") (pinfunction "MGTHRXN0_226_Y1") (pintype "input"))
    )
    (net (code "92") (name "/GT11RX_P") (class "Default")
      (node (ref "IC37") (pin "Y2") (pinfunction "MGTHRXP0_226_Y2") (pintype "input"))
    )
    (net (code "93") (name "/GT11TXC_N") (class "Default")
      (node (ref "C318") (pin "2") (pinfunction "2_2") (pintype "passive"))
      (node (ref "IC37") (pin "AA3") (pinfunction "MGTHTXN0_226_AA3") (pintype "output"))
    )
    (net (code "94") (name "/GT11TXC_P") (class "Default")
      (node (ref "C317") (pin "2") (pinfunction "2_2") (pintype "passive"))
      (node (ref "IC37") (pin "AA4") (pinfunction "MGTHTXP0_226_AA4") (pintype "output"))
    )
    (net (code "95") (name "/GT11TX_N") (class "Default")
      (node (ref "C318") (pin "1") (pinfunction "1_1") (pintype "passive"))
    )
    (net (code "96") (name "/GT11TX_P") (class "Default")
      (node (ref "C317") (pin "1") (pinfunction "1_1") (pintype "passive"))
    )
    (net (code "97") (name "/GT12RX_N") (class "Default")
      (node (ref "IC37") (pin "AB1") (pinfunction "MGTHRXN3_225_AB1") (pintype "input"))
    )
    (net (code "98") (name "/GT12RX_P") (class "Default")
      (node (ref "IC37") (pin "AB2") (pinfunction "MGTHRXP3_225_AB2") (pintype "input"))
    )
    (net (code "99") (name "/GT12TXC_N") (class "Default")
      (node (ref "C326") (pin "2") (pinfunction "2_2") (pintype "passive"))
      (node (ref "IC37") (pin "AC3") (pinfunction "MGTHTXN3_225_AC3") (pintype "output"))
    )
    (net (code "100") (name "/GT12TXC_P") (class "Default")
      (node (ref "C325") (pin "2") (pinfunction "2_2") (pintype "passive"))
      (node (ref "IC37") (pin "AC4") (pinfunction "MGTHTXP3_225_AC4") (pintype "output"))
    )
    (net (code "101") (name "/GT12TX_N") (class "Default")
      (node (ref "C326") (pin "1") (pinfunction "1_1") (pintype "passive"))
    )
    (net (code "102") (name "/GT12TX_P") (class "Default")
      (node (ref "C325") (pin "1") (pinfunction "1_1") (pintype "passive"))
    )
    (net (code "103") (name "/GT13RX_N") (class "Default")
      (node (ref "IC37") (pin "AD1") (pinfunction "MGTHRXN2_225_AD1") (pintype "input"))
    )
    (net (code "104") (name "/GT13RX_P") (class "Default")
      (node (ref "IC37") (pin "AD2") (pinfunction "MGTHRXP2_225_AD2") (pintype "input"))
    )
    (net (code "105") (name "/GT13TXC_N") (class "Default")
      (node (ref "C324") (pin "2") (pinfunction "2_2") (pintype "passive"))
      (node (ref "IC37") (pin "AE3") (pinfunction "MGTHTXN2_225_AE3") (pintype "output"))
    )
    (net (code "106") (name "/GT13TXC_P") (class "Default")
      (node (ref "C323") (pin "2") (pinfunction "2_2") (pintype "passive"))
      (node (ref "IC37") (pin "AE4") (pinfunction "MGTHTXP2_225_AE4") (pintype "output"))
    )
    (net (code "107") (name "/GT13TX_N") (class "Default")
      (node (ref "C324") (pin "1") (pinfunction "1_1") (pintype "passive"))
    )
    (net (code "108") (name "/GT13TX_P") (class "Default")
      (node (ref "C323") (pin "1") (pinfunction "1_1") (pintype "passive"))
    )
    (net (code "109") (name "/GT14RX_N") (class "Default")
      (node (ref "IC37") (pin "AF1") (pinfunction "MGTHRXN1_225_AF1") (pintype "input"))
    )
    (net (code "110") (name "/GT14RX_P") (class "Default")
      (node (ref "IC37") (pin "AF2") (pinfunction "MGTHRXP1_225_AF2") (pintype "input"))
    )
    (net (code "111") (name "/GT14TXC_N") (class "Default")
      (node (ref "C322") (pin "2") (pinfunction "2_2") (pintype "passive"))
      (node (ref "IC37") (pin "AG3") (pinfunction "MGTHTXN1_225_AG3") (pintype "output"))
    )
    (net (code "112") (name "/GT14TXC_P") (class "Default")
      (node (ref "C321") (pin "2") (pinfunction "2_2") (pintype "passive"))
      (node (ref "IC37") (pin "AG4") (pinfunction "MGTHTXP1_225_AG4") (pintype "output"))
    )
    (net (code "113") (name "/GT14TX_N") (class "Default")
      (node (ref "C322") (pin "1") (pinfunction "1_1") (pintype "passive"))
    )
    (net (code "114") (name "/GT14TX_P") (class "Default")
      (node (ref "C321") (pin "1") (pinfunction "1_1") (pintype "passive"))
    )
    (net (code "115") (name "/GT15RX_N") (class "Default")
      (node (ref "IC37") (pin "AH1") (pinfunction "MGTHRXN0_225_AH1") (pintype "input"))
    )
    (net (code "116") (name "/GT15RX_P") (class "Default")
      (node (ref "IC37") (pin "AH2") (pinfunction "MGTHRXP0_225_AH2") (pintype "input"))
    )
    (net (code "117") (name "/GT15TXC_N") (class "Default")
      (node (ref "C320") (pin "2") (pinfunction "2_2") (pintype "passive"))
      (node (ref "IC37") (pin "AH5") (pinfunction "MGTHTXN0_225_AH5") (pintype "output"))
    )
    (net (code "118") (name "/GT15TXC_P") (class "Default")
      (node (ref "C319") (pin "2") (pinfunction "2_2") (pintype "passive"))
      (node (ref "IC37") (pin "AH6") (pinfunction "MGTHTXP0_225_AH6") (pintype "output"))
    )
    (net (code "119") (name "/GT15TX_N") (class "Default")
      (node (ref "C320") (pin "1") (pinfunction "1_1") (pintype "passive"))
    )
    (net (code "120") (name "/GT15TX_P") (class "Default")
      (node (ref "C319") (pin "1") (pinfunction "1_1") (pintype "passive"))
    )
    (net (code "121") (name "/GT16RX_N") (class "Default")
      (node (ref "C331") (pin "2") (pinfunction "2_2") (pintype "passive"))
    )
    (net (code "122") (name "/GT16RX_P") (class "Default")
      (node (ref "C330") (pin "2") (pinfunction "2_2") (pintype "passive"))
    )
    (net (code "123") (name "/GT16TX_N") (class "Default")
      (node (ref "C329") (pin "2") (pinfunction "2_2") (pintype "passive"))
    )
    (net (code "124") (name "/GT16TX_P") (class "Default")
      (node (ref "C332") (pin "2") (pinfunction "2_2") (pintype "passive"))
    )
    (net (code "125") (name "/GT_CLK0_IN_N") (class "Default")
      (node (ref "IC37") (pin "V5") (pinfunction "MGTREFCLK0N_226_V5") (pintype "input"))
    )
    (net (code "126") (name "/GT_CLK0_IN_P") (class "Default")
      (node (ref "IC37") (pin "V6") (pinfunction "MGTREFCLK0P_226_V6") (pintype "input"))
    )
    (net (code "127") (name "/MGT_CDR_CLK_N") (class "Default")
      (node (ref "IC37") (pin "AD5") (pinfunction "MGTREFCLK1N_224_AD5") (pintype "input"))
    )
    (net (code "128") (name "/MGT_CDR_CLK_P") (class "Default")
      (node (ref "IC37") (pin "AD6") (pinfunction "MGTREFCLK1P_224_AD6") (pintype "input"))
    )
    (net (code "129") (name "/OSC3_PWR") (class "Default")
      (node (ref "C285") (pin "2") (pinfunction "2_2") (pintype "passive"))
      (node (ref "L14") (pin "1") (pinfunction "1_1") (pintype "passive"))
      (node (ref "OSC1") (pin "2") (pinfunction "OE_2") (pintype "input"))
      (node (ref "OSC1") (pin "6") (pinfunction "VDD_6") (pintype "power_in"))
    )
    (net (code "130") (name "/OSC4_PWR") (class "Default")
      (node (ref "C288") (pin "2") (pinfunction "2_2") (pintype "passive"))
      (node (ref "L15") (pin "1") (pinfunction "1_1") (pintype "passive"))
      (node (ref "OSC2") (pin "2") (pinfunction "OE_2") (pintype "input"))
      (node (ref "OSC2") (pin "6") (pinfunction "VDD_6") (pintype "power_in"))
    )
    (net (code "131") (name "/REFCLK226_UFL_N") (class "Default")
      (node (ref "C279") (pin "1") (pinfunction "1_1") (pintype "passive"))
      (node (ref "IC37") (pin "T5") (pinfunction "MGTREFCLK1N_226_T5") (pintype "input"))
    )
    (net (code "132") (name "/REFCLK226_UFL_P") (class "Default")
      (node (ref "C280") (pin "1") (pinfunction "1_1") (pintype "passive"))
      (node (ref "IC37") (pin "T6") (pinfunction "MGTREFCLK1P_226_T6") (pintype "input"))
    )
    (net (code "133") (name "/REFCLK228_C_N") (class "Default")
      (node (ref "C284") (pin "1") (pinfunction "1_1") (pintype "passive"))
      (node (ref "IC37") (pin "K5") (pinfunction "MGTREFCLK0N_228_K5") (pintype "input"))
    )
    (net (code "134") (name "/REFCLK228_C_P") (class "Default")
      (node (ref "C283") (pin "1") (pinfunction "1_1") (pintype "passive"))
      (node (ref "IC37") (pin "K6") (pinfunction "MGTREFCLK0P_228_K6") (pintype "input"))
    )
    (net (code "135") (name "/REFCLK228_UFL_N") (class "Default")
      (node (ref "C684") (pin "2") (pinfunction "2_2") (pintype "passive"))
      (node (ref "IC37") (pin "H5") (pinfunction "MGTREFCLK1N_228_H5") (pintype "input"))
    )
    (net (code "136") (name "/REFCLK228_UFL_P") (class "Default")
      (node (ref "C685") (pin "2") (pinfunction "2_2") (pintype "passive"))
      (node (ref "IC37") (pin "H6") (pinfunction "MGTREFCLK1P_228_H6") (pintype "input"))
    )
    (net (code "137") (name "/RX4_N") (class "Default")
      (node (ref "IC37") (pin "AK1") (pinfunction "MGTHRXN2_224_AK1") (pintype "input"))
      (node (ref "J16") (pin "5") (pinfunction "B-_5") (pintype "bidirectional"))
    )
    (net (code "138") (name "/RX4_P") (class "Default")
      (node (ref "IC37") (pin "AK2") (pinfunction "MGTHRXP2_224_AK2") (pintype "input"))
      (node (ref "J16") (pin "6") (pinfunction "B+_6") (pintype "bidirectional"))
    )
    (net (code "139") (name "/RX5C_N") (class "Default")
      (node (ref "C328") (pin "1") (pinfunction "1_1") (pintype "passive"))
      (node (ref "C331") (pin "1") (pinfunction "1_1") (pintype "passive"))
      (node (ref "IC37") (pin "AJ3") (pinfunction "MGTHRXN3_224_AJ3") (pintype "input"))
    )
    (net (code "140") (name "/RX5C_P") (class "Default")
      (node (ref "C327") (pin "1") (pinfunction "1_1") (pintype "passive"))
      (node (ref "C330") (pin "1") (pinfunction "1_1") (pintype "passive"))
      (node (ref "IC37") (pin "AJ4") (pinfunction "MGTHRXP3_224_AJ4") (pintype "input"))
    )
    (net (code "141") (name "/RX5_N") (class "Default")
      (node (ref "C328") (pin "2") (pinfunction "2_2") (pintype "passive"))
      (node (ref "J17") (pin "5") (pinfunction "B-_5") (pintype "bidirectional"))
    )
    (net (code "142") (name "/RX5_P") (class "Default")
      (node (ref "C327") (pin "2") (pinfunction "2_2") (pintype "passive"))
      (node (ref "J17") (pin "6") (pinfunction "B+_6") (pintype "bidirectional"))
    )
    (net (code "143") (name "/SFP0RX_N") (class "Default")
      (node (ref "IC37") (pin "AP1") (pinfunction "MGTHRXN0_224_AP1") (pintype "input"))
    )
    (net (code "144") (name "/SFP0RX_P") (class "Default")
      (node (ref "IC37") (pin "AP2") (pinfunction "MGTHRXP0_224_AP2") (pintype "input"))
    )
    (net (code "145") (name "/SFP0TX_N") (class "Default")
      (node (ref "IC37") (pin "AN3") (pinfunction "MGTHTXN0_224_AN3") (pintype "output"))
    )
    (net (code "146") (name "/SFP0TX_P") (class "Default")
      (node (ref "IC37") (pin "AN4") (pinfunction "MGTHTXP0_224_AN4") (pintype "output"))
    )
    (net (code "147") (name "/SFP1RX_N") (class "Default")
      (node (ref "C349") (pin "2") (pinfunction "2_2") (pintype "passive"))
    )
    (net (code "148") (name "/SFP1RX_P") (class "Default")
      (node (ref "C352") (pin "2") (pinfunction "2_2") (pintype "passive"))
    )
    (net (code "149") (name "/SFP1TX_N") (class "Default")
      (node (ref "C347") (pin "2") (pinfunction "2_2") (pintype "passive"))
    )
    (net (code "150") (name "/SFP1TX_P") (class "Default")
      (node (ref "C348") (pin "2") (pinfunction "2_2") (pintype "passive"))
    )
    (net (code "151") (name "/SFP2RXC_N") (class "Default")
      (node (ref "C335") (pin "1") (pinfunction "1_1") (pintype "passive"))
      (node (ref "C349") (pin "1") (pinfunction "1_1") (pintype "passive"))
      (node (ref "IC37") (pin "AM1") (pinfunction "MGTHRXN1_224_AM1") (pintype "input"))
    )
    (net (code "152") (name "/SFP2RXC_P") (class "Default")
      (node (ref "C336") (pin "1") (pinfunction "1_1") (pintype "passive"))
      (node (ref "C352") (pin "1") (pinfunction "1_1") (pintype "passive"))
      (node (ref "IC37") (pin "AM2") (pinfunction "MGTHRXP1_224_AM2") (pintype "input"))
    )
    (net (code "153") (name "/SFP2TXC_N") (class "Default")
      (node (ref "C333") (pin "1") (pinfunction "1_1") (pintype "passive"))
      (node (ref "C347") (pin "1") (pinfunction "1_1") (pintype "passive"))
      (node (ref "IC37") (pin "AM5") (pinfunction "MGTHTXN1_224_AM5") (pintype "output"))
    )
    (net (code "154") (name "/SFP2TXC_P") (class "Default")
      (node (ref "C334") (pin "1") (pinfunction "1_1") (pintype "passive"))
      (node (ref "C348") (pin "1") (pinfunction "1_1") (pintype "passive"))
      (node (ref "IC37") (pin "AM6") (pinfunction "MGTHTXP1_224_AM6") (pintype "output"))
    )
    (net (code "155") (name "/TX4C_N") (class "Default")
      (node (ref "C294") (pin "1") (pinfunction "1_1") (pintype "passive"))
      (node (ref "IC37") (pin "AL3") (pinfunction "MGTHTXN2_224_AL3") (pintype "output"))
    )
    (net (code "156") (name "/TX4C_P") (class "Default")
      (node (ref "C293") (pin "1") (pinfunction "1_1") (pintype "passive"))
      (node (ref "IC37") (pin "AL4") (pinfunction "MGTHTXP2_224_AL4") (pintype "output"))
    )
    (net (code "157") (name "/TX4_N") (class "Default")
      (node (ref "C294") (pin "2") (pinfunction "2_2") (pintype "passive"))
      (node (ref "J16") (pin "3") (pinfunction "A-_3") (pintype "bidirectional"))
    )
    (net (code "158") (name "/TX4_P") (class "Default")
      (node (ref "C293") (pin "2") (pinfunction "2_2") (pintype "passive"))
      (node (ref "J16") (pin "2") (pinfunction "A+_2") (pintype "bidirectional"))
    )
    (net (code "159") (name "/TX5C_N") (class "Default")
      (node (ref "C292") (pin "1") (pinfunction "1_1") (pintype "passive"))
      (node (ref "C329") (pin "1") (pinfunction "1_1") (pintype "passive"))
      (node (ref "IC37") (pin "AK5") (pinfunction "MGTHTXN3_224_AK5") (pintype "output"))
    )
    (net (code "160") (name "/TX5C_P") (class "Default")
      (node (ref "C291") (pin "1") (pinfunction "1_1") (pintype "passive"))
      (node (ref "C332") (pin "1") (pinfunction "1_1") (pintype "passive"))
      (node (ref "IC37") (pin "AK6") (pinfunction "MGTHTXP3_224_AK6") (pintype "output"))
    )
    (net (code "161") (name "/TX5_N") (class "Default")
      (node (ref "C292") (pin "2") (pinfunction "2_2") (pintype "passive"))
      (node (ref "J17") (pin "3") (pinfunction "A-_3") (pintype "bidirectional"))
    )
    (net (code "162") (name "/TX5_P") (class "Default")
      (node (ref "C291") (pin "2") (pinfunction "2_2") (pintype "passive"))
      (node (ref "J17") (pin "2") (pinfunction "A+_2") (pintype "bidirectional"))
    )
    (net (code "169") (name "GND") (class "Default")
      (node (ref "C285") (pin "1") (pinfunction "1_1") (pintype "passive"))
      (node (ref "C288") (pin "1") (pinfunction "1_1") (pintype "passive"))
      (node (ref "J16") (pin "1") (pinfunction "GND_1") (pintype "power_in"))
      (node (ref "J16") (pin "4") (pinfunction "GND_4") (pintype "power_in"))
      (node (ref "J16") (pin "7") (pinfunction "GND_7") (pintype "power_in"))
      (node (ref "J17") (pin "1") (pinfunction "GND_1") (pintype "power_in"))
      (node (ref "J17") (pin "4") (pinfunction "GND_4") (pintype "power_in"))
      (node (ref "J17") (pin "7") (pinfunction "GND_7") (pintype "power_in"))
      (node (ref "J21") (pin "2") (pinfunction "2_2") (pintype "bidirectional"))
      (node (ref "J22") (pin "2") (pinfunction "2_2") (pintype "bidirectional"))
      (node (ref "J23") (pin "2") (pinfunction "2_2") (pintype "bidirectional"))
      (node (ref "J24") (pin "2") (pinfunction "2_2") (pintype "bidirectional"))
      (node (ref "J25") (pin "2") (pinfunction "2_2") (pintype "bidirectional"))
      (node (ref "J26") (pin "2") (pinfunction "2_2") (pintype "bidirectional"))
      (node (ref "OSC1") (pin "3") (pinfunction "GND_3") (pintype "power_in"))
      (node (ref "OSC2") (pin "3") (pinfunction "GND_3") (pintype "power_in"))
      (node (ref "R352") (pin "1") (pinfunction "1_1") (pintype "passive"))
      (node (ref "R353") (pin "1") (pinfunction "1_1") (pintype "passive"))
      (node (ref "R354") (pin "1") (pinfunction "1_1") (pintype "passive"))
      (node (ref "R355") (pin "1") (pinfunction "1_1") (pintype "passive"))
    )
    (net (code "170") (name "Net-(C279-Pad2)") (class "Default")
      (node (ref "C279") (pin "2") (pinfunction "2_2") (pintype "passive"))
      (node (ref "J24") (pin "1") (pinfunction "1_1") (pintype "bidirectional"))
    )
    (net (code "171") (name "Net-(C280-Pad2)") (class "Default")
      (node (ref "C280") (pin "2") (pinfunction "2_2") (pintype "passive"))
      (node (ref "J23") (pin "1") (pinfunction "1_1") (pintype "bidirectional"))
    )
    (net (code "172") (name "Net-(C283-Pad2)") (class "Default")
      (node (ref "C283") (pin "2") (pinfunction "2_2") (pintype "passive"))
      (node (ref "J25") (pin "1") (pinfunction "1_1") (pintype "bidirectional"))
    )
    (net (code "173") (name "Net-(C284-Pad2)") (class "Default")
      (node (ref "C284") (pin "2") (pinfunction "2_2") (pintype "passive"))
      (node (ref "J26") (pin "1") (pinfunction "1_1") (pintype "bidirectional"))
    )
    (net (code "174") (name "Net-(C286-Pad1)") (class "Default")
      (node (ref "C286") (pin "1") (pinfunction "1_1") (pintype "passive"))
      (node (ref "R298") (pin "2") (pinfunction "2_2") (pintype "passive"))
    )
    (net (code "175") (name "Net-(C287-Pad1)") (class "Default")
      (node (ref "C287") (pin "1") (pinfunction "1_1") (pintype "passive"))
      (node (ref "R299") (pin "2") (pinfunction "2_2") (pintype "passive"))
    )
    (net (code "176") (name "Net-(C684-Pad1)") (class "Default")
      (node (ref "C684") (pin "1") (pinfunction "1_1") (pintype "passive"))
      (node (ref "J21") (pin "1") (pinfunction "1_1") (pintype "bidirectional"))
    )
    (net (code "177") (name "Net-(C685-Pad1)") (class "Default")
      (node (ref "C685") (pin "1") (pinfunction "1_1") (pintype "passive"))
      (node (ref "J22") (pin "1") (pinfunction "1_1") (pintype "bidirectional"))
    )
    (net (code "178") (name "Net-(OSC1-CLK+)") (class "Default")
      (node (ref "OSC1") (pin "4") (pinfunction "CLK+_4") (pintype "output"))
      (node (ref "R300") (pin "1") (pinfunction "1_1") (pintype "passive"))
      (node (ref "R354") (pin "2") (pinfunction "2_2") (pintype "passive"))
    )
    (net (code "179") (name "Net-(OSC1-CLK-)") (class "Default")
      (node (ref "OSC1") (pin "5") (pinfunction "CLK-_5") (pintype "output"))
      (node (ref "R303") (pin "1") (pinfunction "1_1") (pintype "passive"))
      (node (ref "R355") (pin "2") (pinfunction "2_2") (pintype "passive"))
    )
    (net (code "180") (name "Net-(OSC2-CLK+)") (class "Default")
      (node (ref "OSC2") (pin "4") (pinfunction "CLK+_4") (pintype "output"))
      (node (ref "R298") (pin "1") (pinfunction "1_1") (pintype "passive"))
      (node (ref "R352") (pin "2") (pinfunction "2_2") (pintype "passive"))
    )
    (net (code "181") (name "Net-(OSC2-CLK-)") (class "Default")
      (node (ref "OSC2") (pin "5") (pinfunction "CLK-_5") (pintype "output"))
      (node (ref "R299") (pin "1") (pinfunction "1_1") (pintype "passive"))
      (node (ref "R353") (pin "2") (pinfunction "2_2") (pintype "passive"))
    )
    (net (code "182") (name "P3V3") (class "Default")
      (node (ref "L14") (pin "2") (pinfunction "2_2") (pintype "passive"))
      (node (ref "L15") (pin "2") (pinfunction "2_2") (pintype "passive"))
    )
    (net (code "183") (name "unconnected-(OSC1-NC-Pad1)") (class "Default")
      (node (ref "OSC1") (pin "1") (pinfunction "NC_1") (pintype "passive"))
    )
    (net (code "184") (name "unconnected-(OSC2-NC-Pad1)") (class "Default")
      (node (ref "OSC2") (pin "1") (pinfunction "NC_1") (pintype "passive"))
    )
  )
)
